# module.net
KiCad netlist of a schematic drawn in EAGLE
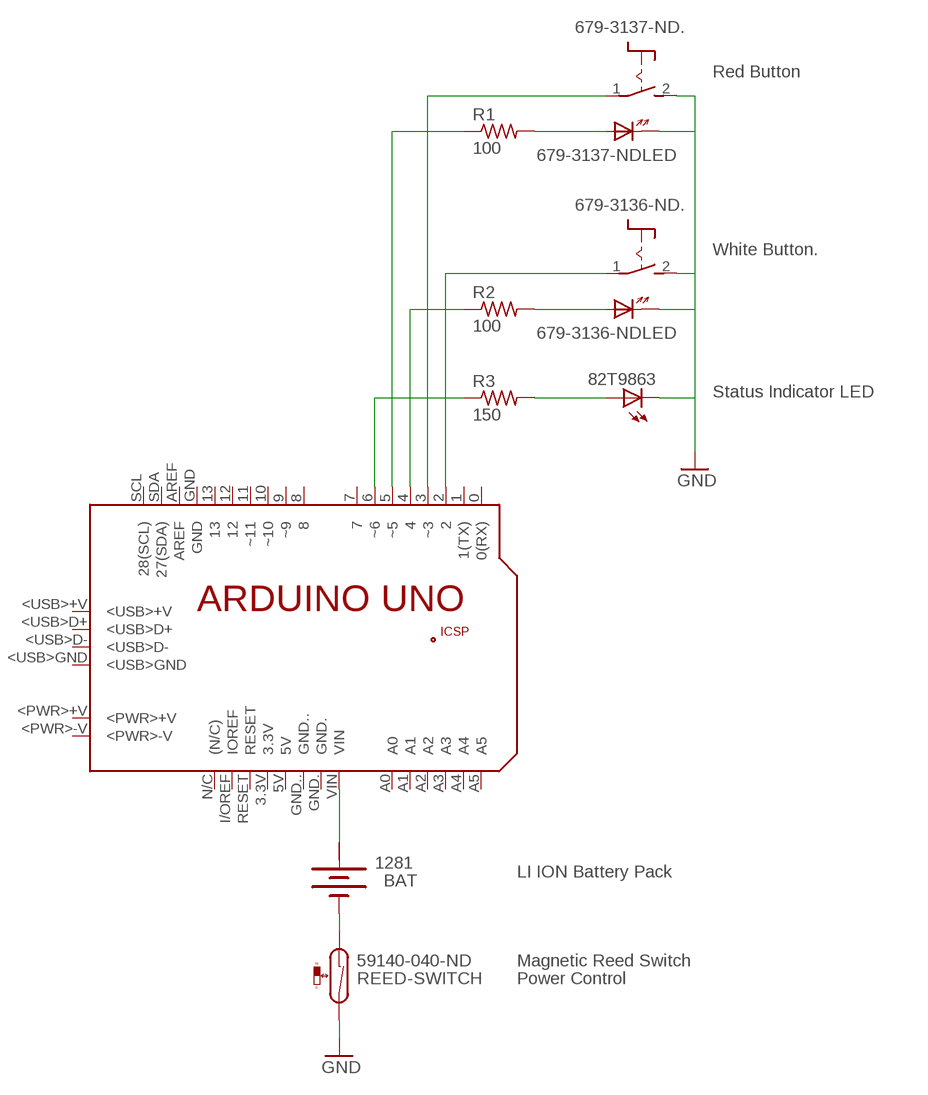
[diagram p0: schematic, sheet 1]

(export (version "E")
  (design (tool "Eeschema 10.0.6"))
  (components
    (comp (ref "82T9863")
      (value "LEDSQR5.7X3.2")
      (footprint "eagle-import:U57X32")
      (libsource (lib "eagle-import") (part "LEDSQR5.7X3.2"))
    )
    (comp (ref "679-3136-ND")
      (value "MARQ6425")
      (footprint "eagle-import:MARQ6425")
      (libsource (lib "eagle-import") (part "MARQ6425"))
    )
    (comp (ref "679-3137-ND")
      (value "MARQ6425")
      (footprint "eagle-import:MARQ6425")
      (libsource (lib "eagle-import") (part "MARQ6425"))
    )
    (comp (ref "1281")
      (value "BAT")
      (footprint "eagle-import:BATTERY")
      (libsource (lib "eagle-import") (part "BATTERY"))
    )
    (comp (ref "59140-040-ND")
      (value "REED-SWITCH")
      (footprint "eagle-import:MK6-4")
      (libsource (lib "eagle-import") (part "REED-SWITCH-MK6-4"))
    )
    (comp (ref "PCB1")
      (value "ARDUINO_UNO")
      (footprint "eagle-import:ARDUINO_UNO")
      (libsource (lib "eagle-import") (part "ARDUINO_UNO"))
    )
    (comp (ref "R1")
      (value "100")
      (footprint "eagle-import:0204V")
      (libsource (lib "eagle-import") (part "R-US_0204/2V"))
    )
    (comp (ref "R2")
      (value "100")
      (footprint "eagle-import:0204V")
      (libsource (lib "eagle-import") (part "R-US_0204/2V"))
    )
    (comp (ref "R3")
      (value "150")
      (footprint "eagle-import:0204V")
      (libsource (lib "eagle-import") (part "R-US_0204/2V"))
    )
  )
  (nets
    (net (code "1") (name "/+") (class "Default")
      (node (ref "1281") (pin "+@1") (pinfunction "+_+@1") (pintype "power_in"))
    )
    (net (code "2") (name "GND") (class "Default")
      (node (ref "59140-040-ND") (pin "2") (pinfunction "2_2") (pintype "passive"))
      (node (ref "679-3136-ND") (pin "2") (pinfunction "S_2") (pintype "passive"))
      (node (ref "679-3136-ND") (pin "K") (pinfunction "K_K") (pintype "passive"))
      (node (ref "679-3137-ND") (pin "2") (pinfunction "S_2") (pintype "passive"))
      (node (ref "679-3137-ND") (pin "K") (pinfunction "K_K") (pintype "passive"))
      (node (ref "82T9863") (pin "K") (pinfunction "C_K") (pintype "passive"))
    )
    (net (code "3") (name "Net-(82T9863-PadA)") (class "Default")
      (node (ref "82T9863") (pin "A") (pinfunction "A_A") (pintype "passive"))
      (node (ref "R3") (pin "2") (pinfunction "2_2") (pintype "passive"))
    )
    (net (code "4") (name "Net-(679-3136-ND-PadA)") (class "Default")
      (node (ref "679-3136-ND") (pin "A") (pinfunction "A_A") (pintype "passive"))
      (node (ref "R2") (pin "2") (pinfunction "2_2") (pintype "passive"))
    )
    (net (code "5") (name "Net-(679-3136-NDA-P)") (class "Default")
      (node (ref "679-3136-ND") (pin "1") (pinfunction "P_1") (pintype "passive"))
      (node (ref "PCB1") (pin "2") (pinfunction "2_2") (pintype "bidirectional"))
    )
    (net (code "6") (name "Net-(679-3137-ND-PadA)") (class "Default")
      (node (ref "679-3137-ND") (pin "A") (pinfunction "A_A") (pintype "passive"))
      (node (ref "R1") (pin "2") (pinfunction "2_2") (pintype "passive"))
    )
    (net (code "7") (name "Net-(679-3137-NDA-P)") (class "Default")
      (node (ref "679-3137-ND") (pin "1") (pinfunction "P_1") (pintype "passive"))
      (node (ref "PCB1") (pin "3") (pinfunction "~{3}_3") (pintype "bidirectional"))
    )
    (net (code "8") (name "Net-(1281-Pad+)") (class "Default")
      (node (ref "1281") (pin "+") (pinfunction "+_+") (pintype "power_in"))
      (node (ref "PCB1") (pin "VIN") (pinfunction "VIN_VIN") (pintype "bidirectional"))
    )
    (net (code "9") (name "Net-(1281-Pad-)") (class "Default")
      (node (ref "1281") (pin "-") (pinfunction "-_-") (pintype "power_in"))
      (node (ref "59140-040-ND") (pin "1") (pinfunction "1_1") (pintype "passive"))
    )
    (net (code "10") (name "Net-(PCB1-Pad4)") (class "Default")
      (node (ref "PCB1") (pin "4") (pinfunction "4_4") (pintype "bidirectional"))
      (node (ref "R2") (pin "1") (pinfunction "1_1") (pintype "passive"))
    )
    (net (code "11") (name "Net-(PCB1-~{5})") (class "Default")
      (node (ref "PCB1") (pin "5") (pinfunction "~{5}_5") (pintype "bidirectional"))
      (node (ref "R1") (pin "1") (pinfunction "1_1") (pintype "passive"))
    )
    (net (code "12") (name "Net-(PCB1-~{6})") (class "Default")
      (node (ref "PCB1") (pin "6") (pinfunction "~{6}_6") (pintype "bidirectional"))
      (node (ref "R3") (pin "1") (pinfunction "1_1") (pintype "passive"))
    )
    (net (code "13") (name "unconnected-(PCB1-(N{slash}C)-PadN{slash}C)") (class "Default")
      (node (ref "PCB1") (pin "N/C") (pinfunction "(N/C)_N/C") (pintype "bidirectional"))
    )
    (net (code "14") (name "unconnected-(PCB1-0(RX)-Pad0)") (class "Default")
      (node (ref "PCB1") (pin "0") (pinfunction "0(RX)_0") (pintype "bidirectional"))
    )
    (net (code "15") (name "unconnected-(PCB1-1(TX)-Pad1)") (class "Default")
      (node (ref "PCB1") (pin "1") (pinfunction "1(TX)_1") (pintype "bidirectional"))
    )
    (net (code "16") (name "unconnected-(PCB1-27(SDA)-PadSDA)") (class "Default")
      (node (ref "PCB1") (pin "SDA") (pinfunction "27(SDA)_SDA") (pintype "bidirectional"))
    )
    (net (code "17") (name "unconnected-(PCB1-28(SCL)-PadSCL)") (class "Default")
      (node (ref "PCB1") (pin "SCL") (pinfunction "28(SCL)_SCL") (pintype "bidirectional"))
    )
    (net (code "18") (name "unconnected-(PCB1-IOREF-PadI{slash}OREF)") (class "Default")
      (node (ref "PCB1") (pin "I/OREF") (pinfunction "IOREF_I/OREF") (pintype "bidirectional"))
    )
    (net (code "19") (name "unconnected-(PCB1-Pad+5V)") (class "Default")
      (node (ref "PCB1") (pin "+5V") (pinfunction "+5V_+5V") (pintype "bidirectional"))
    )
    (net (code "20") (name "unconnected-(PCB1-Pad3.3V)") (class "Default")
      (node (ref "PCB1") (pin "3.3V") (pinfunction "3.3V_3.3V") (pintype "bidirectional"))
    )
    (net (code "21") (name "unconnected-(PCB1-Pad5V)") (class "Default")
      (node (ref "PCB1") (pin "5V") (pinfunction "5V_5V") (pintype "bidirectional"))
    )
    (net (code "22") (name "unconnected-(PCB1-Pad7)") (class "Default")
      (node (ref "PCB1") (pin "7") (pinfunction "7_7") (pintype "bidirectional"))
    )
    (net (code "23") (name "unconnected-(PCB1-Pad8)") (class "Default")
      (node (ref "PCB1") (pin "8") (pinfunction "8_8") (pintype "bidirectional"))
    )
    (net (code "24") (name "unconnected-(PCB1-Pad12)") (class "Default")
      (node (ref "PCB1") (pin "12") (pinfunction "12_12") (pintype "bidirectional"))
    )
    (net (code "25") (name "unconnected-(PCB1-Pad13)") (class "Default")
      (node (ref "PCB1") (pin "13") (pinfunction "13_13") (pintype "bidirectional"))
    )
    (net (code "26") (name "unconnected-(PCB1-Pad<PWR>+V)") (class "Default")
      (node (ref "PCB1") (pin "<PWR>+V") (pinfunction "<PWR>+V_<PWR>+V") (pintype "bidirectional"))
    )
    (net (code "27") (name "unconnected-(PCB1-Pad<PWR>-V)") (class "Default")
      (node (ref "PCB1") (pin "<PWR>-V") (pinfunction "<PWR>-V_<PWR>-V") (pintype "bidirectional"))
    )
    (net (code "28") (name "unconnected-(PCB1-Pad<USB>+V)") (class "Default")
      (node (ref "PCB1") (pin "<USB>+V") (pinfunction "<USB>+V_<USB>+V") (pintype "bidirectional"))
    )
    (net (code "29") (name "unconnected-(PCB1-Pad<USB>D+)") (class "Default")
      (node (ref "PCB1") (pin "<USB>D+") (pinfunction "<USB>D+_<USB>D+") (pintype "bidirectional"))
    )
    (net (code "30") (name "unconnected-(PCB1-Pad<USB>D-)") (class "Default")
      (node (ref "PCB1") (pin "<USB>D-") (pinfunction "<USB>D-_<USB>D-") (pintype "bidirectional"))
    )
    (net (code "31") (name "unconnected-(PCB1-Pad<USB>GND)") (class "Default")
      (node (ref "PCB1") (pin "<USB>GND") (pinfunction "<USB>GND_<USB>GND") (pintype "bidirectional"))
    )
    (net (code "32") (name "unconnected-(PCB1-PadA0)") (class "Default")
      (node (ref "PCB1") (pin "A0") (pinfunction "A0_A0") (pintype "bidirectional"))
    )
    (net (code "33") (name "unconnected-(PCB1-PadA1)") (class "Default")
      (node (ref "PCB1") (pin "A1") (pinfunction "A1_A1") (pintype "bidirectional"))
    )
    (net (code "34") (name "unconnected-(PCB1-PadA2)") (class "Default")
      (node (ref "PCB1") (pin "A2") (pinfunction "A2_A2") (pintype "bidirectional"))
    )
    (net (code "35") (name "unconnected-(PCB1-PadA3)") (class "Default")
      (node (ref "PCB1") (pin "A3") (pinfunction "A3_A3") (pintype "bidirectional"))
    )
    (net (code "36") (name "unconnected-(PCB1-PadA4)") (class "Default")
      (node (ref "PCB1") (pin "A4") (pinfunction "A4_A4") (pintype "bidirectional"))
    )
    (net (code "37") (name "unconnected-(PCB1-PadA5)") (class "Default")
      (node (ref "PCB1") (pin "A5") (pinfunction "A5_A5") (pintype "bidirectional"))
    )
    (net (code "38") (name "unconnected-(PCB1-PadAREF)") (class "Default")
      (node (ref "PCB1") (pin "AREF") (pinfunction "AREF_AREF") (pintype "bidirectional"))
    )
    (net (code "39") (name "unconnected-(PCB1-PadGND)") (class "Default")
      (node (ref "PCB1") (pin "GND") (pinfunction "GND_GND") (pintype "bidirectional"))
    )
    (net (code "40") (name "unconnected-(PCB1-PadGND.)") (class "Default")
      (node (ref "PCB1") (pin "GND.") (pinfunction "GND._GND.") (pintype "bidirectional"))
    )
    (net (code "41") (name "unconnected-(PCB1-PadGND..)") (class "Default")
      (node (ref "PCB1") (pin "GND..") (pinfunction "GND.._GND..") (pintype "bidirectional"))
    )
    (net (code "42") (name "unconnected-(PCB1-PadGND_)") (class "Default")
      (node (ref "PCB1") (pin "GND_") (pinfunction "GND__GND_") (pintype "bidirectional"))
    )
    (net (code "43") (name "unconnected-(PCB1-PadMISO)") (class "Default")
      (node (ref "PCB1") (pin "MISO") (pinfunction "MISO_MISO") (pintype "bidirectional"))
    )
    (net (code "44") (name "unconnected-(PCB1-PadMOSI)") (class "Default")
      (node (ref "PCB1") (pin "MOSI") (pinfunction "MOSI_MOSI") (pintype "bidirectional"))
    )
    (net (code "45") (name "unconnected-(PCB1-PadRESET)") (class "Default")
      (node (ref "PCB1") (pin "RESET") (pinfunction "RESET_RESET") (pintype "bidirectional"))
    )
    (net (code "46") (name "unconnected-(PCB1-PadRESET.)") (class "Default")
      (node (ref "PCB1") (pin "RESET.") (pinfunction "RESET._RESET.") (pintype "bidirectional"))
    )
    (net (code "47") (name "unconnected-(PCB1-PadSCK)") (class "Default")
      (node (ref "PCB1") (pin "SCK") (pinfunction "SCK_SCK") (pintype "bidirectional"))
    )
    (net (code "48") (name "unconnected-(PCB1-~{9}-Pad9)") (class "Default")
      (node (ref "PCB1") (pin "9") (pinfunction "~{9}_9") (pintype "bidirectional"))
    )
    (net (code "49") (name "unconnected-(PCB1-~{10}-Pad10)") (class "Default")
      (node (ref "PCB1") (pin "10") (pinfunction "~{10}_10") (pintype "bidirectional"))
    )
    (net (code "50") (name "unconnected-(PCB1-~{11}-Pad11)") (class "Default")
      (node (ref "PCB1") (pin "11") (pinfunction "~{11}_11") (pintype "bidirectional"))
    )
  )
)
